# Schematic.net
KiCad netlist of a schematic drawn in Altium Designer
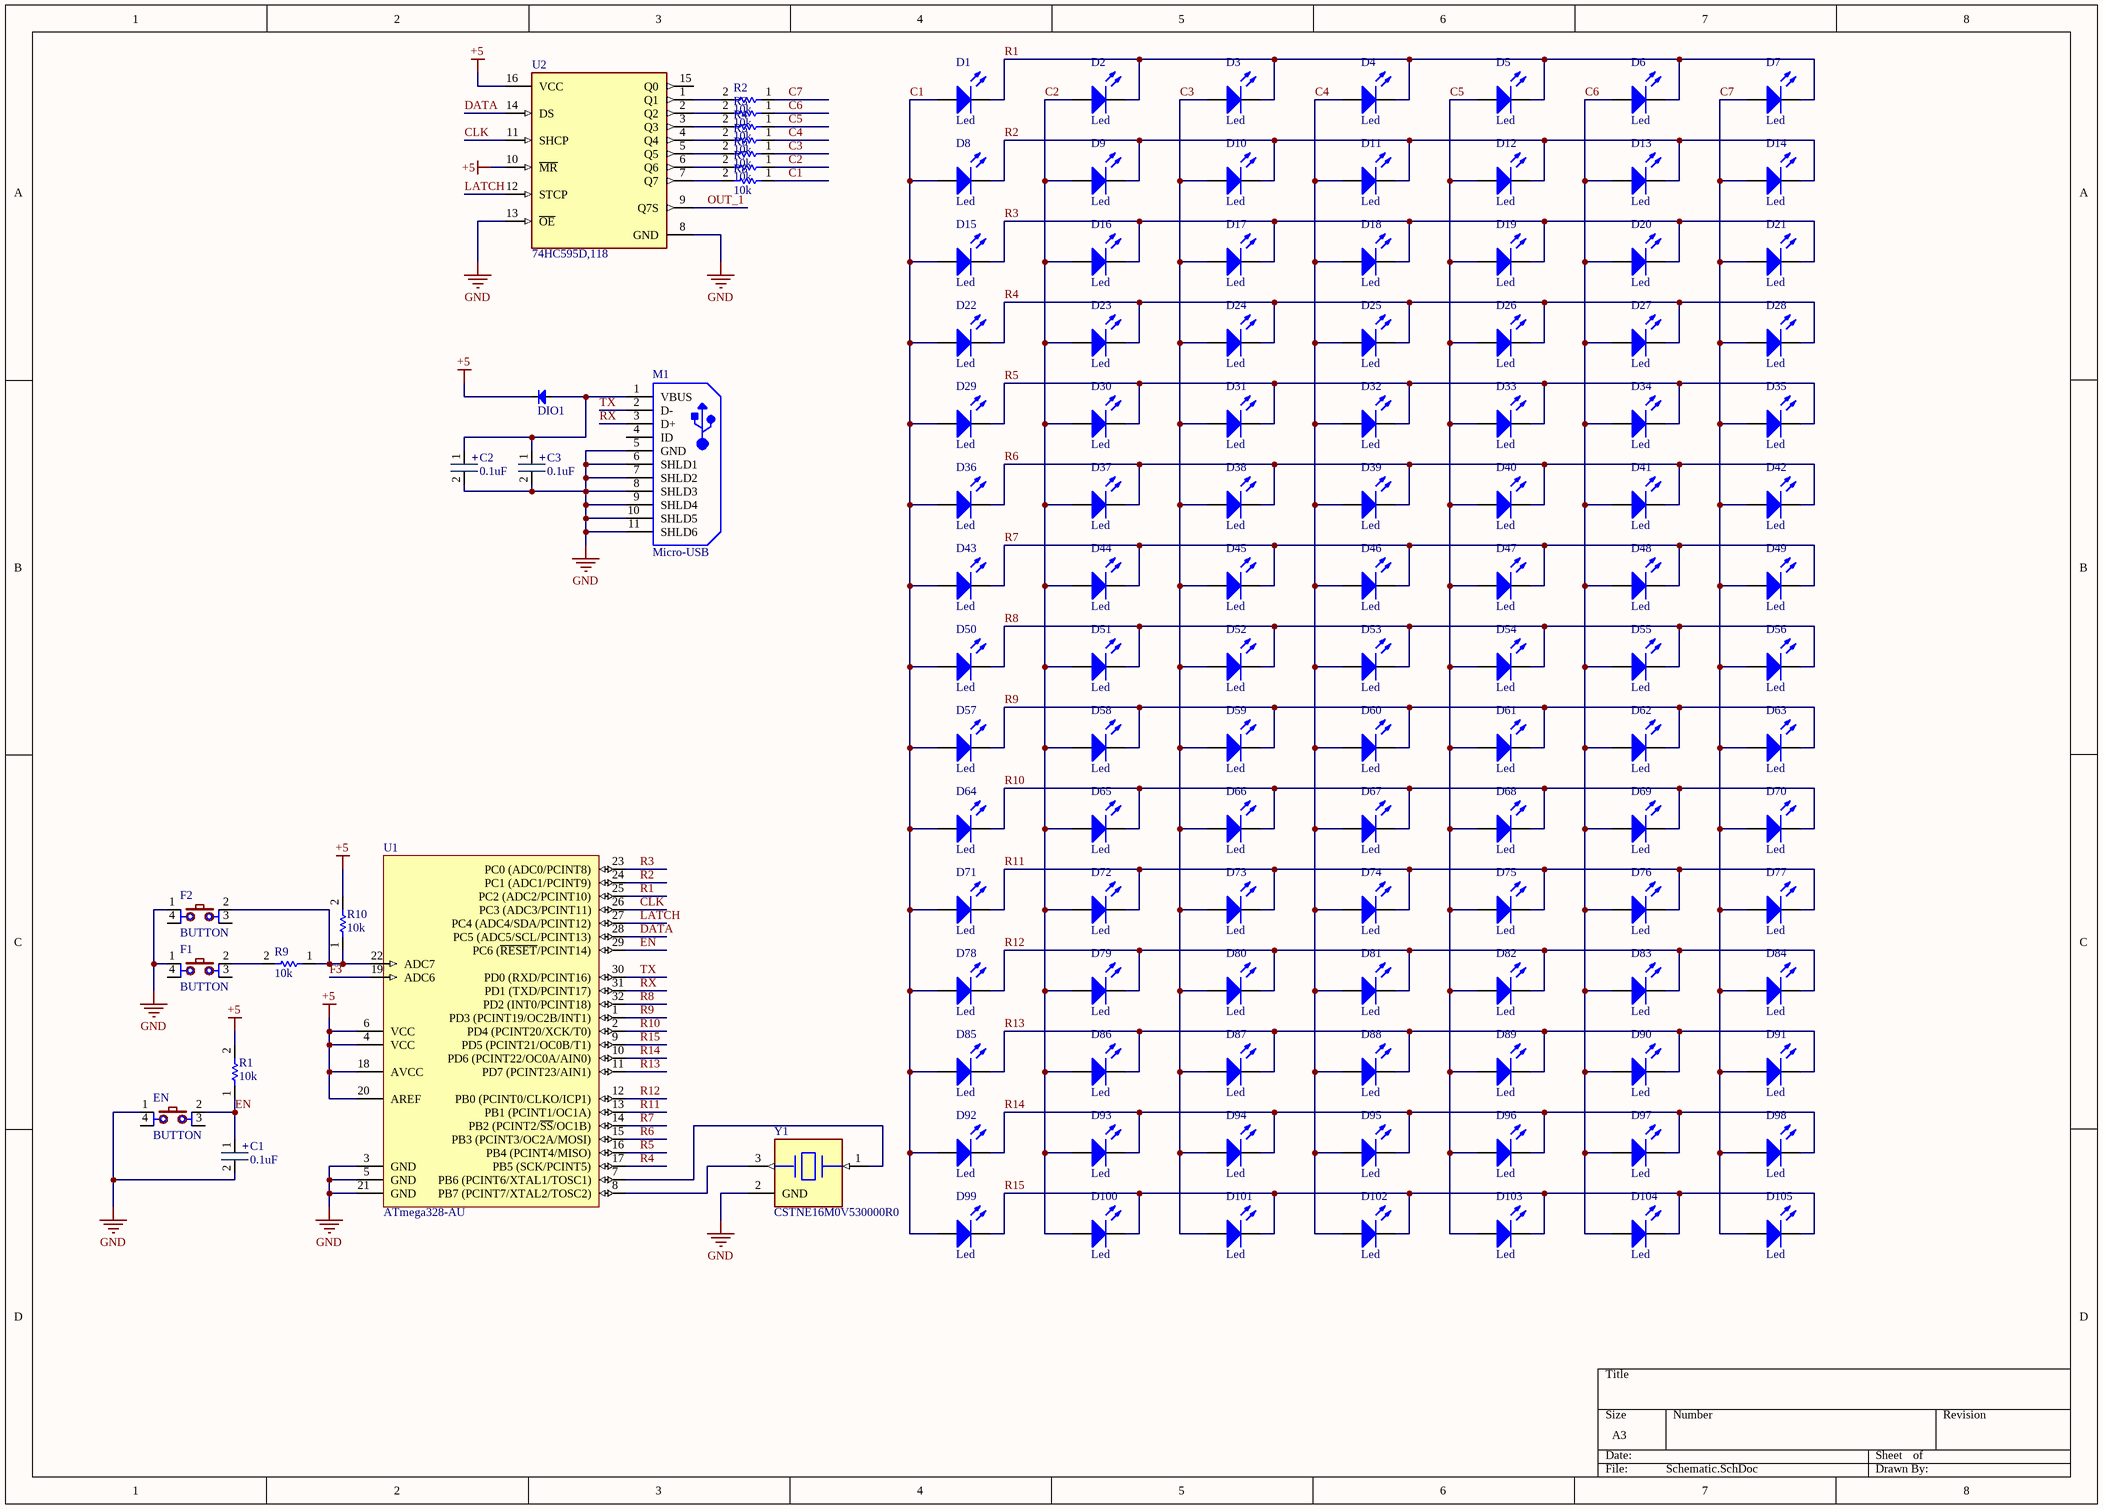
[diagram p0: Schematic.SchDoc]

(export (version "E")
  (design (tool "Eeschema 10.0.6"))
  (components
    (comp (ref "C1")
      (value "0.1uF")
      (footprint "Cap_0603_A")
      (description "General Purpose Ceramic Capacitor, 0603, 1nF, 10%, X7R, 15%, 50V")
      (fields (field (name "VOLTAGE") "50V") (field (name "TOLERANCE") "10%"))
      (libsource (lib "ResCapTransDio") (part "Capacitor"))
    )
    (comp (ref "C2")
      (value "0.1uF")
      (footprint "Cap_0603_A")
      (description "General Purpose Ceramic Capacitor, 0603, 1nF, 10%, X7R, 15%, 50V")
      (fields (field (name "VOLTAGE") "50V") (field (name "TOLERANCE") "10%"))
      (libsource (lib "ResCapTransDio") (part "Capacitor"))
    )
    (comp (ref "C3")
      (value "0.1uF")
      (footprint "Cap_0603_A")
      (description "General Purpose Ceramic Capacitor, 0603, 1nF, 10%, X7R, 15%, 50V")
      (fields (field (name "VOLTAGE") "50V") (field (name "TOLERANCE") "10%"))
      (libsource (lib "ResCapTransDio") (part "Capacitor"))
    )
    (comp (ref "D1") (value "Led") (footprint "LED 0603") (libsource (lib "ResCapTransDio") (part "Led")))
    (comp (ref "D2") (value "Led") (footprint "LED 0603") (libsource (lib "ResCapTransDio") (part "Led")))
    (comp (ref "D3") (value "Led") (footprint "LED 0603") (libsource (lib "ResCapTransDio") (part "Led")))
    (comp (ref "D4") (value "Led") (footprint "LED 0603") (libsource (lib "ResCapTransDio") (part "Led")))
    (comp (ref "D5") (value "Led") (footprint "LED 0603") (libsource (lib "ResCapTransDio") (part "Led")))
    (comp (ref "D6") (value "Led") (footprint "LED 0603") (libsource (lib "ResCapTransDio") (part "Led")))
    (comp (ref "D7") (value "Led") (footprint "LED 0603") (libsource (lib "ResCapTransDio") (part "Led")))
    (comp (ref "D8") (value "Led") (footprint "LED 0603") (libsource (lib "ResCapTransDio") (part "Led")))
    (comp (ref "D9") (value "Led") (footprint "LED 0603") (libsource (lib "ResCapTransDio") (part "Led")))
    (comp (ref "D10") (value "Led") (footprint "LED 0603") (libsource (lib "ResCapTransDio") (part "Led")))
    (comp (ref "D11") (value "Led") (footprint "LED 0603") (libsource (lib "ResCapTransDio") (part "Led")))
    (comp (ref "D12") (value "Led") (footprint "LED 0603") (libsource (lib "ResCapTransDio") (part "Led")))
    (comp (ref "D13") (value "Led") (footprint "LED 0603") (libsource (lib "ResCapTransDio") (part "Led")))
    (comp (ref "D14") (value "Led") (footprint "LED 0603") (libsource (lib "ResCapTransDio") (part "Led")))
    (comp (ref "D15") (value "Led") (footprint "LED 0603") (libsource (lib "ResCapTransDio") (part "Led")))
    (comp (ref "D16") (value "Led") (footprint "LED 0603") (libsource (lib "ResCapTransDio") (part "Led")))
    (comp (ref "D17") (value "Led") (footprint "LED 0603") (libsource (lib "ResCapTransDio") (part "Led")))
    (comp (ref "D18") (value "Led") (footprint "LED 0603") (libsource (lib "ResCapTransDio") (part "Led")))
    (comp (ref "D19") (value "Led") (footprint "LED 0603") (libsource (lib "ResCapTransDio") (part "Led")))
    (comp (ref "D20") (value "Led") (footprint "LED 0603") (libsource (lib "ResCapTransDio") (part "Led")))
    (comp (ref "D21") (value "Led") (footprint "LED 0603") (libsource (lib "ResCapTransDio") (part "Led")))
    (comp (ref "D22") (value "Led") (footprint "LED 0603") (libsource (lib "ResCapTransDio") (part "Led")))
    (comp (ref "D23") (value "Led") (footprint "LED 0603") (libsource (lib "ResCapTransDio") (part "Led")))
    (comp (ref "D24") (value "Led") (footprint "LED 0603") (libsource (lib "ResCapTransDio") (part "Led")))
    (comp (ref "D25") (value "Led") (footprint "LED 0603") (libsource (lib "ResCapTransDio") (part "Led")))
    (comp (ref "D26") (value "Led") (footprint "LED 0603") (libsource (lib "ResCapTransDio") (part "Led")))
    (comp (ref "D27") (value "Led") (footprint "LED 0603") (libsource (lib "ResCapTransDio") (part "Led")))
    (comp (ref "D28") (value "Led") (footprint "LED 0603") (libsource (lib "ResCapTransDio") (part "Led")))
    (comp (ref "D29") (value "Led") (footprint "LED 0603") (libsource (lib "ResCapTransDio") (part "Led")))
    (comp (ref "D30") (value "Led") (footprint "LED 0603") (libsource (lib "ResCapTransDio") (part "Led")))
    (comp (ref "D31") (value "Led") (footprint "LED 0603") (libsource (lib "ResCapTransDio") (part "Led")))
    (comp (ref "D32") (value "Led") (footprint "LED 0603") (libsource (lib "ResCapTransDio") (part "Led")))
    (comp (ref "D33") (value "Led") (footprint "LED 0603") (libsource (lib "ResCapTransDio") (part "Led")))
    (comp (ref "D34") (value "Led") (footprint "LED 0603") (libsource (lib "ResCapTransDio") (part "Led")))
    (comp (ref "D35") (value "Led") (footprint "LED 0603") (libsource (lib "ResCapTransDio") (part "Led")))
    (comp (ref "D36") (value "Led") (footprint "LED 0603") (libsource (lib "ResCapTransDio") (part "Led")))
    (comp (ref "D37") (value "Led") (footprint "LED 0603") (libsource (lib "ResCapTransDio") (part "Led")))
    (comp (ref "D38") (value "Led") (footprint "LED 0603") (libsource (lib "ResCapTransDio") (part "Led")))
    (comp (ref "D39") (value "Led") (footprint "LED 0603") (libsource (lib "ResCapTransDio") (part "Led")))
    (comp (ref "D40") (value "Led") (footprint "LED 0603") (libsource (lib "ResCapTransDio") (part "Led")))
    (comp (ref "D41") (value "Led") (footprint "LED 0603") (libsource (lib "ResCapTransDio") (part "Led")))
    (comp (ref "D42") (value "Led") (footprint "LED 0603") (libsource (lib "ResCapTransDio") (part "Led")))
    (comp (ref "D43") (value "Led") (footprint "LED 0603") (libsource (lib "ResCapTransDio") (part "Led")))
    (comp (ref "D44") (value "Led") (footprint "LED 0603") (libsource (lib "ResCapTransDio") (part "Led")))
    (comp (ref "D45") (value "Led") (footprint "LED 0603") (libsource (lib "ResCapTransDio") (part "Led")))
    (comp (ref "D46") (value "Led") (footprint "LED 0603") (libsource (lib "ResCapTransDio") (part "Led")))
    (comp (ref "D47") (value "Led") (footprint "LED 0603") (libsource (lib "ResCapTransDio") (part "Led")))
    (comp (ref "D48") (value "Led") (footprint "LED 0603") (libsource (lib "ResCapTransDio") (part "Led")))
    (comp (ref "D49") (value "Led") (footprint "LED 0603") (libsource (lib "ResCapTransDio") (part "Led")))
    (comp (ref "D50") (value "Led") (footprint "LED 0603") (libsource (lib "ResCapTransDio") (part "Led")))
    (comp (ref "D51") (value "Led") (footprint "LED 0603") (libsource (lib "ResCapTransDio") (part "Led")))
    (comp (ref "D52") (value "Led") (footprint "LED 0603") (libsource (lib "ResCapTransDio") (part "Led")))
    (comp (ref "D53") (value "Led") (footprint "LED 0603") (libsource (lib "ResCapTransDio") (part "Led")))
    (comp (ref "D54") (value "Led") (footprint "LED 0603") (libsource (lib "ResCapTransDio") (part "Led")))
    (comp (ref "D55") (value "Led") (footprint "LED 0603") (libsource (lib "ResCapTransDio") (part "Led")))
    (comp (ref "D56") (value "Led") (footprint "LED 0603") (libsource (lib "ResCapTransDio") (part "Led")))
    (comp (ref "D57") (value "Led") (footprint "LED 0603") (libsource (lib "ResCapTransDio") (part "Led")))
    (comp (ref "D58") (value "Led") (footprint "LED 0603") (libsource (lib "ResCapTransDio") (part "Led")))
    (comp (ref "D59") (value "Led") (footprint "LED 0603") (libsource (lib "ResCapTransDio") (part "Led")))
    (comp (ref "D60") (value "Led") (footprint "LED 0603") (libsource (lib "ResCapTransDio") (part "Led")))
    (comp (ref "D61") (value "Led") (footprint "LED 0603") (libsource (lib "ResCapTransDio") (part "Led")))
    (comp (ref "D62") (value "Led") (footprint "LED 0603") (libsource (lib "ResCapTransDio") (part "Led")))
    (comp (ref "D63") (value "Led") (footprint "LED 0603") (libsource (lib "ResCapTransDio") (part "Led")))
    (comp (ref "D64") (value "Led") (footprint "LED 0603") (libsource (lib "ResCapTransDio") (part "Led")))
    (comp (ref "D65") (value "Led") (footprint "LED 0603") (libsource (lib "ResCapTransDio") (part "Led")))
    (comp (ref "D66") (value "Led") (footprint "LED 0603") (libsource (lib "ResCapTransDio") (part "Led")))
    (comp (ref "D67") (value "Led") (footprint "LED 0603") (libsource (lib "ResCapTransDio") (part "Led")))
    (comp (ref "D68") (value "Led") (footprint "LED 0603") (libsource (lib "ResCapTransDio") (part "Led")))
    (comp (ref "D69") (value "Led") (footprint "LED 0603") (libsource (lib "ResCapTransDio") (part "Led")))
    (comp (ref "D70") (value "Led") (footprint "LED 0603") (libsource (lib "ResCapTransDio") (part "Led")))
    (comp (ref "D71") (value "Led") (footprint "LED 0603") (libsource (lib "ResCapTransDio") (part "Led")))
    (comp (ref "D72") (value "Led") (footprint "LED 0603") (libsource (lib "ResCapTransDio") (part "Led")))
    (comp (ref "D73") (value "Led") (footprint "LED 0603") (libsource (lib "ResCapTransDio") (part "Led")))
    (comp (ref "D74") (value "Led") (footprint "LED 0603") (libsource (lib "ResCapTransDio") (part "Led")))
    (comp (ref "D75") (value "Led") (footprint "LED 0603") (libsource (lib "ResCapTransDio") (part "Led")))
    (comp (ref "D76") (value "Led") (footprint "LED 0603") (libsource (lib "ResCapTransDio") (part "Led")))
    (comp (ref "D77") (value "Led") (footprint "LED 0603") (libsource (lib "ResCapTransDio") (part "Led")))
    (comp (ref "D78") (value "Led") (footprint "LED 0603") (libsource (lib "ResCapTransDio") (part "Led")))
    (comp (ref "D79") (value "Led") (footprint "LED 0603") (libsource (lib "ResCapTransDio") (part "Led")))
    (comp (ref "D80") (value "Led") (footprint "LED 0603") (libsource (lib "ResCapTransDio") (part "Led")))
    (comp (ref "D81") (value "Led") (footprint "LED 0603") (libsource (lib "ResCapTransDio") (part "Led")))
    (comp (ref "D82") (value "Led") (footprint "LED 0603") (libsource (lib "ResCapTransDio") (part "Led")))
    (comp (ref "D83") (value "Led") (footprint "LED 0603") (libsource (lib "ResCapTransDio") (part "Led")))
    (comp (ref "D84") (value "Led") (footprint "LED 0603") (libsource (lib "ResCapTransDio") (part "Led")))
    (comp (ref "D85") (value "Led") (footprint "LED 0603") (libsource (lib "ResCapTransDio") (part "Led")))
    (comp (ref "D86") (value "Led") (footprint "LED 0603") (libsource (lib "ResCapTransDio") (part "Led")))
    (comp (ref "D87") (value "Led") (footprint "LED 0603") (libsource (lib "ResCapTransDio") (part "Led")))
    (comp (ref "D88") (value "Led") (footprint "LED 0603") (libsource (lib "ResCapTransDio") (part "Led")))
    (comp (ref "D89") (value "Led") (footprint "LED 0603") (libsource (lib "ResCapTransDio") (part "Led")))
    (comp (ref "D90") (value "Led") (footprint "LED 0603") (libsource (lib "ResCapTransDio") (part "Led")))
    (comp (ref "D91") (value "Led") (footprint "LED 0603") (libsource (lib "ResCapTransDio") (part "Led")))
    (comp (ref "D92") (value "Led") (footprint "LED 0603") (libsource (lib "ResCapTransDio") (part "Led")))
    (comp (ref "D93") (value "Led") (footprint "LED 0603") (libsource (lib "ResCapTransDio") (part "Led")))
    (comp (ref "D94") (value "Led") (footprint "LED 0603") (libsource (lib "ResCapTransDio") (part "Led")))
    (comp (ref "D95") (value "Led") (footprint "LED 0603") (libsource (lib "ResCapTransDio") (part "Led")))
    (comp (ref "D96") (value "Led") (footprint "LED 0603") (libsource (lib "ResCapTransDio") (part "Led")))
    (comp (ref "D97") (value "Led") (footprint "LED 0603") (libsource (lib "ResCapTransDio") (part "Led")))
    (comp (ref "D98") (value "Led") (footprint "LED 0603") (libsource (lib "ResCapTransDio") (part "Led")))
    (comp (ref "D99") (value "Led") (footprint "LED 0603") (libsource (lib "ResCapTransDio") (part "Led")))
    (comp (ref "D100") (value "Led") (footprint "LED 0603") (libsource (lib "ResCapTransDio") (part "Led")))
    (comp (ref "D101") (value "Led") (footprint "LED 0603") (libsource (lib "ResCapTransDio") (part "Led")))
    (comp (ref "D102") (value "Led") (footprint "LED 0603") (libsource (lib "ResCapTransDio") (part "Led")))
    (comp (ref "D103") (value "Led") (footprint "LED 0603") (libsource (lib "ResCapTransDio") (part "Led")))
    (comp (ref "D104") (value "Led") (footprint "LED 0603") (libsource (lib "ResCapTransDio") (part "Led")))
    (comp (ref "D105") (value "Led") (footprint "LED 0603") (libsource (lib "ResCapTransDio") (part "Led")))
    (comp (ref "DIO1")
      (value "Diode SMD")
      (footprint "DIO-SMD-106")
      (description "Default Diode")
      (fields (field (name "PUBLISHER") "Altium Limited"))
      (libsource (lib "TechMT.VN_Lib_Project v2") (part "Diode SMD"))
    )
    (comp (ref "EN")
      (value "BUTTON")
      (footprint "BUTTON 3x4mm 2 Pin")
      (libsource (lib "Librarys") (part "BUTTON 4 PIN"))
    )
    (comp (ref "F1")
      (value "BUTTON")
      (footprint "BUTTON 3x4mm 2 Pin")
      (libsource (lib "Librarys") (part "BUTTON 4 PIN"))
    )
    (comp (ref "F2")
      (value "BUTTON")
      (footprint "BUTTON 3x4mm 2 Pin")
      (libsource (lib "Librarys") (part "BUTTON 4 PIN"))
    )
    (comp (ref "M1")
      (value "Micro-USB")
      (footprint "2.0 5 PIN SMD")
      (libsource (lib "Librarys") (part "Micro-USB"))
    )
    (comp (ref "R1")
      (value "10k")
      (footprint "Res_0603")
      (libsource (lib "ResCapTransDio") (part "Resistor"))
    )
    (comp (ref "R2")
      (value "10k")
      (footprint "Res_0603")
      (libsource (lib "ResCapTransDio") (part "Resistor"))
    )
    (comp (ref "R3")
      (value "10k")
      (footprint "Res_0603")
      (libsource (lib "ResCapTransDio") (part "Resistor"))
    )
    (comp (ref "R4")
      (value "10k")
      (footprint "Res_0603")
      (libsource (lib "ResCapTransDio") (part "Resistor"))
    )
    (comp (ref "R5")
      (value "10k")
      (footprint "Res_0603")
      (libsource (lib "ResCapTransDio") (part "Resistor"))
    )
    (comp (ref "R6")
      (value "10k")
      (footprint "Res_0603")
      (libsource (lib "ResCapTransDio") (part "Resistor"))
    )
    (comp (ref "R7")
      (value "10k")
      (footprint "Res_0603")
      (libsource (lib "ResCapTransDio") (part "Resistor"))
    )
    (comp (ref "R8")
      (value "10k")
      (footprint "Res_0603")
      (libsource (lib "ResCapTransDio") (part "Resistor"))
    )
    (comp (ref "R9")
      (value "10k")
      (footprint "Res_0603")
      (libsource (lib "ResCapTransDio") (part "Resistor"))
    )
    (comp (ref "R10")
      (value "10k")
      (footprint "Res_0603")
      (libsource (lib "ResCapTransDio") (part "Resistor"))
    )
    (comp (ref "U1")
      (value "ATmega328-AU")
      (footprint "TQFP32")
      (fields (field (name "PUBLISHER") "Altium Limited"))
      (libsource (lib "TechMT.VN_Lib_Project v2") (part "ATmega328-AU"))
    )
    (comp (ref "U2")
      (value "74HC595D,118")
      (footprint "FP-SOT109-1-IPC_C")
      (description "IC SHIFT REGISTER 8BIT 16SOIC")
      (libsource (lib "Altium Content Vault") (part "7b153f231cfcc3ac06dee253bd56617"))
    )
    (comp (ref "Y1")
      (value "CSTNE16M0V530000R0")
      (footprint "FP-CSTNE16M0V530000R0-MFG")
      (description "CERAMIC RES 16.0000MHZ 15PF SMD")
      (fields (field (name "TOLERANCE") "0.5%") (field (name "MANUFACTURER") "Murata"))
      (libsource (lib "Altium Content Vault") (part "f88508b02107a2c8e6f46217c19d2b8"))
    )
  )
  (nets
    (net (code "1") (name "+5") (class "Default")
      (node (ref "DIO1") (pin "2") (pinfunction "K_2") (pintype "passive"))
      (node (ref "R1") (pin "2") (pinfunction "2_2") (pintype "passive"))
      (node (ref "R10") (pin "2") (pinfunction "2_2") (pintype "passive"))
      (node (ref "U1") (pin "18") (pinfunction "AVCC_18") (pintype "power_in"))
      (node (ref "U1") (pin "20") (pinfunction "AREF_20") (pintype "passive"))
      (node (ref "U1") (pin "4") (pinfunction "VCC_4") (pintype "power_in"))
      (node (ref "U1") (pin "6") (pinfunction "VCC_6") (pintype "power_in"))
      (node (ref "U2") (pin "10") (pinfunction "~{MR}_10") (pintype "input"))
      (node (ref "U2") (pin "16") (pinfunction "VCC_16") (pintype "power_in"))
    )
    (net (code "2") (name "/C1") (class "Default")
      (node (ref "D1") (pin "1") (pinfunction "A_1") (pintype "passive"))
      (node (ref "D15") (pin "1") (pinfunction "A_1") (pintype "passive"))
      (node (ref "D22") (pin "1") (pinfunction "A_1") (pintype "passive"))
      (node (ref "D29") (pin "1") (pinfunction "A_1") (pintype "passive"))
      (node (ref "D36") (pin "1") (pinfunction "A_1") (pintype "passive"))
      (node (ref "D43") (pin "1") (pinfunction "A_1") (pintype "passive"))
      (node (ref "D50") (pin "1") (pinfunction "A_1") (pintype "passive"))
      (node (ref "D57") (pin "1") (pinfunction "A_1") (pintype "passive"))
      (node (ref "D64") (pin "1") (pinfunction "A_1") (pintype "passive"))
      (node (ref "D71") (pin "1") (pinfunction "A_1") (pintype "passive"))
      (node (ref "D78") (pin "1") (pinfunction "A_1") (pintype "passive"))
      (node (ref "D8") (pin "1") (pinfunction "A_1") (pintype "passive"))
      (node (ref "D85") (pin "1") (pinfunction "A_1") (pintype "passive"))
      (node (ref "D92") (pin "1") (pinfunction "A_1") (pintype "passive"))
      (node (ref "D99") (pin "1") (pinfunction "A_1") (pintype "passive"))
      (node (ref "R8") (pin "1") (pinfunction "1_1") (pintype "passive"))
    )
    (net (code "3") (name "/C2") (class "Default")
      (node (ref "D100") (pin "1") (pinfunction "A_1") (pintype "passive"))
      (node (ref "D16") (pin "1") (pinfunction "A_1") (pintype "passive"))
      (node (ref "D2") (pin "1") (pinfunction "A_1") (pintype "passive"))
      (node (ref "D23") (pin "1") (pinfunction "A_1") (pintype "passive"))
      (node (ref "D30") (pin "1") (pinfunction "A_1") (pintype "passive"))
      (node (ref "D37") (pin "1") (pinfunction "A_1") (pintype "passive"))
      (node (ref "D44") (pin "1") (pinfunction "A_1") (pintype "passive"))
      (node (ref "D51") (pin "1") (pinfunction "A_1") (pintype "passive"))
      (node (ref "D58") (pin "1") (pinfunction "A_1") (pintype "passive"))
      (node (ref "D65") (pin "1") (pinfunction "A_1") (pintype "passive"))
      (node (ref "D72") (pin "1") (pinfunction "A_1") (pintype "passive"))
      (node (ref "D79") (pin "1") (pinfunction "A_1") (pintype "passive"))
      (node (ref "D86") (pin "1") (pinfunction "A_1") (pintype "passive"))
      (node (ref "D9") (pin "1") (pinfunction "A_1") (pintype "passive"))
      (node (ref "D93") (pin "1") (pinfunction "A_1") (pintype "passive"))
      (node (ref "R7") (pin "1") (pinfunction "1_1") (pintype "passive"))
    )
    (net (code "4") (name "/C3") (class "Default")
      (node (ref "D10") (pin "1") (pinfunction "A_1") (pintype "passive"))
      (node (ref "D101") (pin "1") (pinfunction "A_1") (pintype "passive"))
      (node (ref "D17") (pin "1") (pinfunction "A_1") (pintype "passive"))
      (node (ref "D24") (pin "1") (pinfunction "A_1") (pintype "passive"))
      (node (ref "D3") (pin "1") (pinfunction "A_1") (pintype "passive"))
      (node (ref "D31") (pin "1") (pinfunction "A_1") (pintype "passive"))
      (node (ref "D38") (pin "1") (pinfunction "A_1") (pintype "passive"))
      (node (ref "D45") (pin "1") (pinfunction "A_1") (pintype "passive"))
      (node (ref "D52") (pin "1") (pinfunction "A_1") (pintype "passive"))
      (node (ref "D59") (pin "1") (pinfunction "A_1") (pintype "passive"))
      (node (ref "D66") (pin "1") (pinfunction "A_1") (pintype "passive"))
      (node (ref "D73") (pin "1") (pinfunction "A_1") (pintype "passive"))
      (node (ref "D80") (pin "1") (pinfunction "A_1") (pintype "passive"))
      (node (ref "D87") (pin "1") (pinfunction "A_1") (pintype "passive"))
      (node (ref "D94") (pin "1") (pinfunction "A_1") (pintype "passive"))
      (node (ref "R6") (pin "1") (pinfunction "1_1") (pintype "passive"))
    )
    (net (code "5") (name "/C4") (class "Default")
      (node (ref "D102") (pin "1") (pinfunction "A_1") (pintype "passive"))
      (node (ref "D11") (pin "1") (pinfunction "A_1") (pintype "passive"))
      (node (ref "D18") (pin "1") (pinfunction "A_1") (pintype "passive"))
      (node (ref "D25") (pin "1") (pinfunction "A_1") (pintype "passive"))
      (node (ref "D32") (pin "1") (pinfunction "A_1") (pintype "passive"))
      (node (ref "D39") (pin "1") (pinfunction "A_1") (pintype "passive"))
      (node (ref "D4") (pin "1") (pinfunction "A_1") (pintype "passive"))
      (node (ref "D46") (pin "1") (pinfunction "A_1") (pintype "passive"))
      (node (ref "D53") (pin "1") (pinfunction "A_1") (pintype "passive"))
      (node (ref "D60") (pin "1") (pinfunction "A_1") (pintype "passive"))
      (node (ref "D67") (pin "1") (pinfunction "A_1") (pintype "passive"))
      (node (ref "D74") (pin "1") (pinfunction "A_1") (pintype "passive"))
      (node (ref "D81") (pin "1") (pinfunction "A_1") (pintype "passive"))
      (node (ref "D88") (pin "1") (pinfunction "A_1") (pintype "passive"))
      (node (ref "D95") (pin "1") (pinfunction "A_1") (pintype "passive"))
      (node (ref "R5") (pin "1") (pinfunction "1_1") (pintype "passive"))
    )
    (net (code "6") (name "/C5") (class "Default")
      (node (ref "D103") (pin "1") (pinfunction "A_1") (pintype "passive"))
      (node (ref "D12") (pin "1") (pinfunction "A_1") (pintype "passive"))
      (node (ref "D19") (pin "1") (pinfunction "A_1") (pintype "passive"))
      (node (ref "D26") (pin "1") (pinfunction "A_1") (pintype "passive"))
      (node (ref "D33") (pin "1") (pinfunction "A_1") (pintype "passive"))
      (node (ref "D40") (pin "1") (pinfunction "A_1") (pintype "passive"))
      (node (ref "D47") (pin "1") (pinfunction "A_1") (pintype "passive"))
      (node (ref "D5") (pin "1") (pinfunction "A_1") (pintype "passive"))
      (node (ref "D54") (pin "1") (pinfunction "A_1") (pintype "passive"))
      (node (ref "D61") (pin "1") (pinfunction "A_1") (pintype "passive"))
      (node (ref "D68") (pin "1") (pinfunction "A_1") (pintype "passive"))
      (node (ref "D75") (pin "1") (pinfunction "A_1") (pintype "passive"))
      (node (ref "D82") (pin "1") (pinfunction "A_1") (pintype "passive"))
      (node (ref "D89") (pin "1") (pinfunction "A_1") (pintype "passive"))
      (node (ref "D96") (pin "1") (pinfunction "A_1") (pintype "passive"))
      (node (ref "R4") (pin "1") (pinfunction "1_1") (pintype "passive"))
    )
    (net (code "7") (name "/C6") (class "Default")
      (node (ref "D104") (pin "1") (pinfunction "A_1") (pintype "passive"))
      (node (ref "D13") (pin "1") (pinfunction "A_1") (pintype "passive"))
      (node (ref "D20") (pin "1") (pinfunction "A_1") (pintype "passive"))
      (node (ref "D27") (pin "1") (pinfunction "A_1") (pintype "passive"))
      (node (ref "D34") (pin "1") (pinfunction "A_1") (pintype "passive"))
      (node (ref "D41") (pin "1") (pinfunction "A_1") (pintype "passive"))
      (node (ref "D48") (pin "1") (pinfunction "A_1") (pintype "passive"))
      (node (ref "D55") (pin "1") (pinfunction "A_1") (pintype "passive"))
      (node (ref "D6") (pin "1") (pinfunction "A_1") (pintype "passive"))
      (node (ref "D62") (pin "1") (pinfunction "A_1") (pintype "passive"))
      (node (ref "D69") (pin "1") (pinfunction "A_1") (pintype "passive"))
      (node (ref "D76") (pin "1") (pinfunction "A_1") (pintype "passive"))
      (node (ref "D83") (pin "1") (pinfunction "A_1") (pintype "passive"))
      (node (ref "D90") (pin "1") (pinfunction "A_1") (pintype "passive"))
      (node (ref "D97") (pin "1") (pinfunction "A_1") (pintype "passive"))
      (node (ref "R3") (pin "1") (pinfunction "1_1") (pintype "passive"))
    )
    (net (code "8") (name "/C7") (class "Default")
      (node (ref "D105") (pin "1") (pinfunction "A_1") (pintype "passive"))
      (node (ref "D14") (pin "1") (pinfunction "A_1") (pintype "passive"))
      (node (ref "D21") (pin "1") (pinfunction "A_1") (pintype "passive"))
      (node (ref "D28") (pin "1") (pinfunction "A_1") (pintype "passive"))
      (node (ref "D35") (pin "1") (pinfunction "A_1") (pintype "passive"))
      (node (ref "D42") (pin "1") (pinfunction "A_1") (pintype "passive"))
      (node (ref "D49") (pin "1") (pinfunction "A_1") (pintype "passive"))
      (node (ref "D56") (pin "1") (pinfunction "A_1") (pintype "passive"))
      (node (ref "D63") (pin "1") (pinfunction "A_1") (pintype "passive"))
      (node (ref "D7") (pin "1") (pinfunction "A_1") (pintype "passive"))
      (node (ref "D70") (pin "1") (pinfunction "A_1") (pintype "passive"))
      (node (ref "D77") (pin "1") (pinfunction "A_1") (pintype "passive"))
      (node (ref "D84") (pin "1") (pinfunction "A_1") (pintype "passive"))
      (node (ref "D91") (pin "1") (pinfunction "A_1") (pintype "passive"))
      (node (ref "D98") (pin "1") (pinfunction "A_1") (pintype "passive"))
      (node (ref "R2") (pin "1") (pinfunction "1_1") (pintype "passive"))
    )
    (net (code "9") (name "/CLK") (class "Default")
      (node (ref "U1") (pin "26") (pinfunction "PC3_(ADC3/PCINT11)_26") (pintype "bidirectional"))
      (node (ref "U2") (pin "11") (pinfunction "SHCP_11") (pintype "input"))
    )
    (net (code "10") (name "/DATA") (class "Default")
      (node (ref "U1") (pin "28") (pinfunction "PC5_(ADC5/SCL/PCINT13)_28") (pintype "bidirectional"))
      (node (ref "U2") (pin "14") (pinfunction "DS_14") (pintype "input"))
    )
    (net (code "11") (name "/EN") (class "Default")
      (node (ref "C1") (pin "1") (pinfunction "1_1") (pintype "passive"))
      (node (ref "EN") (pin "2") (pinfunction "2_2") (pintype "passive"))
      (node (ref "R1") (pin "1") (pinfunction "1_1") (pintype "passive"))
      (node (ref "U1") (pin "29") (pinfunction "PC6_(~{RESET}/PCINT14)_29") (pintype "bidirectional"))
    )
    (net (code "12") (name "/F3") (class "Default")
      (node (ref "U1") (pin "19") (pinfunction "ADC6_19") (pintype "input"))
    )
    (net (code "13") (name "/LATCH") (class "Default")
      (node (ref "U1") (pin "27") (pinfunction "PC4_(ADC4/SDA/PCINT12)_27") (pintype "bidirectional"))
      (node (ref "U2") (pin "12") (pinfunction "STCP_12") (pintype "input"))
    )
    (net (code "14") (name "/OUT_1") (class "Default")
      (node (ref "U2") (pin "9") (pinfunction "Q7S_9") (pintype "output"))
    )
    (net (code "15") (name "/R1") (class "Default")
      (node (ref "D1") (pin "2") (pinfunction "K_2") (pintype "passive"))
      (node (ref "D2") (pin "2") (pinfunction "K_2") (pintype "passive"))
      (node (ref "D3") (pin "2") (pinfunction "K_2") (pintype "passive"))
      (node (ref "D4") (pin "2") (pinfunction "K_2") (pintype "passive"))
      (node (ref "D5") (pin "2") (pinfunction "K_2") (pintype "passive"))
      (node (ref "D6") (pin "2") (pinfunction "K_2") (pintype "passive"))
      (node (ref "D7") (pin "2") (pinfunction "K_2") (pintype "passive"))
      (node (ref "U1") (pin "25") (pinfunction "PC2_(ADC2/PCINT10)_25") (pintype "bidirectional"))
    )
    (net (code "16") (name "/R2") (class "Default")
      (node (ref "D10") (pin "2") (pinfunction "K_2") (pintype "passive"))
      (node (ref "D11") (pin "2") (pinfunction "K_2") (pintype "passive"))
      (node (ref "D12") (pin "2") (pinfunction "K_2") (pintype "passive"))
      (node (ref "D13") (pin "2") (pinfunction "K_2") (pintype "passive"))
      (node (ref "D14") (pin "2") (pinfunction "K_2") (pintype "passive"))
      (node (ref "D8") (pin "2") (pinfunction "K_2") (pintype "passive"))
      (node (ref "D9") (pin "2") (pinfunction "K_2") (pintype "passive"))
      (node (ref "U1") (pin "24") (pinfunction "PC1_(ADC1/PCINT9)_24") (pintype "bidirectional"))
    )
    (net (code "17") (name "/R3") (class "Default")
      (node (ref "D15") (pin "2") (pinfunction "K_2") (pintype "passive"))
      (node (ref "D16") (pin "2") (pinfunction "K_2") (pintype "passive"))
      (node (ref "D17") (pin "2") (pinfunction "K_2") (pintype "passive"))
      (node (ref "D18") (pin "2") (pinfunction "K_2") (pintype "passive"))
      (node (ref "D19") (pin "2") (pinfunction "K_2") (pintype "passive"))
      (node (ref "D20") (pin "2") (pinfunction "K_2") (pintype "passive"))
      (node (ref "D21") (pin "2") (pinfunction "K_2") (pintype "passive"))
      (node (ref "U1") (pin "23") (pinfunction "PC0_(ADC0/PCINT8)_23") (pintype "bidirectional"))
    )
    (net (code "18") (name "/R4") (class "Default")
      (node (ref "D22") (pin "2") (pinfunction "K_2") (pintype "passive"))
      (node (ref "D23") (pin "2") (pinfunction "K_2") (pintype "passive"))
      (node (ref "D24") (pin "2") (pinfunction "K_2") (pintype "passive"))
      (node (ref "D25") (pin "2") (pinfunction "K_2") (pintype "passive"))
      (node (ref "D26") (pin "2") (pinfunction "K_2") (pintype "passive"))
      (node (ref "D27") (pin "2") (pinfunction "K_2") (pintype "passive"))
      (node (ref "D28") (pin "2") (pinfunction "K_2") (pintype "passive"))
      (node (ref "U1") (pin "17") (pinfunction "PB5_(SCK/PCINT5)_17") (pintype "bidirectional"))
    )
    (net (code "19") (name "/R5") (class "Default")
      (node (ref "D29") (pin "2") (pinfunction "K_2") (pintype "passive"))
      (node (ref "D30") (pin "2") (pinfunction "K_2") (pintype "passive"))
      (node (ref "D31") (pin "2") (pinfunction "K_2") (pintype "passive"))
      (node (ref "D32") (pin "2") (pinfunction "K_2") (pintype "passive"))
      (node (ref "D33") (pin "2") (pinfunction "K_2") (pintype "passive"))
      (node (ref "D34") (pin "2") (pinfunction "K_2") (pintype "passive"))
      (node (ref "D35") (pin "2") (pinfunction "K_2") (pintype "passive"))
      (node (ref "U1") (pin "16") (pinfunction "PB4_(PCINT4/MISO)_16") (pintype "bidirectional"))
    )
    (net (code "20") (name "/R6") (class "Default")
      (node (ref "D36") (pin "2") (pinfunction "K_2") (pintype "passive"))
      (node (ref "D37") (pin "2") (pinfunction "K_2") (pintype "passive"))
      (node (ref "D38") (pin "2") (pinfunction "K_2") (pintype "passive"))
      (node (ref "D39") (pin "2") (pinfunction "K_2") (pintype "passive"))
      (node (ref "D40") (pin "2") (pinfunction "K_2") (pintype "passive"))
      (node (ref "D41") (pin "2") (pinfunction "K_2") (pintype "passive"))
      (node (ref "D42") (pin "2") (pinfunction "K_2") (pintype "passive"))
      (node (ref "U1") (pin "15") (pinfunction "PB3_(PCINT3/OC2A/MOSI)_15") (pintype "bidirectional"))
    )
    (net (code "21") (name "/R7") (class "Default")
      (node (ref "D43") (pin "2") (pinfunction "K_2") (pintype "passive"))
      (node (ref "D44") (pin "2") (pinfunction "K_2") (pintype "passive"))
      (node (ref "D45") (pin "2") (pinfunction "K_2") (pintype "passive"))
      (node (ref "D46") (pin "2") (pinfunction "K_2") (pintype "passive"))
      (node (ref "D47") (pin "2") (pinfunction "K_2") (pintype "passive"))
      (node (ref "D48") (pin "2") (pinfunction "K_2") (pintype "passive"))
      (node (ref "D49") (pin "2") (pinfunction "K_2") (pintype "passive"))
      (node (ref "U1") (pin "14") (pinfunction "PB2_(PCINT2/~{SS}/OC1B)_14") (pintype "bidirectional"))
    )
    (net (code "22") (name "/R8") (class "Default")
      (node (ref "D50") (pin "2") (pinfunction "K_2") (pintype "passive"))
      (node (ref "D51") (pin "2") (pinfunction "K_2") (pintype "passive"))
      (node (ref "D52") (pin "2") (pinfunction "K_2") (pintype "passive"))
      (node (ref "D53") (pin "2") (pinfunction "K_2") (pintype "passive"))
      (node (ref "D54") (pin "2") (pinfunction "K_2") (pintype "passive"))
      (node (ref "D55") (pin "2") (pinfunction "K_2") (pintype "passive"))
      (node (ref "D56") (pin "2") (pinfunction "K_2") (pintype "passive"))
      (node (ref "U1") (pin "32") (pinfunction "PD2_(INT0/PCINT18)_32") (pintype "bidirectional"))
    )
    (net (code "23") (name "/R9") (class "Default")
      (node (ref "D57") (pin "2") (pinfunction "K_2") (pintype "passive"))
      (node (ref "D58") (pin "2") (pinfunction "K_2") (pintype "passive"))
      (node (ref "D59") (pin "2") (pinfunction "K_2") (pintype "passive"))
      (node (ref "D60") (pin "2") (pinfunction "K_2") (pintype "passive"))
      (node (ref "D61") (pin "2") (pinfunction "K_2") (pintype "passive"))
      (node (ref "D62") (pin "2") (pinfunction "K_2") (pintype "passive"))
      (node (ref "D63") (pin "2") (pinfunction "K_2") (pintype "passive"))
      (node (ref "U1") (pin "1") (pinfunction "PD3_(PCINT19/OC2B/INT1)_1") (pintype "bidirectional"))
    )
    (net (code "24") (name "/R10") (class "Default")
      (node (ref "D64") (pin "2") (pinfunction "K_2") (pintype "passive"))
      (node (ref "D65") (pin "2") (pinfunction "K_2") (pintype "passive"))
      (node (ref "D66") (pin "2") (pinfunction "K_2") (pintype "passive"))
      (node (ref "D67") (pin "2") (pinfunction "K_2") (pintype "passive"))
      (node (ref "D68") (pin "2") (pinfunction "K_2") (pintype "passive"))
      (node (ref "D69") (pin "2") (pinfunction "K_2") (pintype "passive"))
      (node (ref "D70") (pin "2") (pinfunction "K_2") (pintype "passive"))
      (node (ref "U1") (pin "2") (pinfunction "PD4_(PCINT20/XCK/T0)_2") (pintype "bidirectional"))
    )
    (net (code "25") (name "/R11") (class "Default")
      (node (ref "D71") (pin "2") (pinfunction "K_2") (pintype "passive"))
      (node (ref "D72") (pin "2") (pinfunction "K_2") (pintype "passive"))
      (node (ref "D73") (pin "2") (pinfunction "K_2") (pintype "passive"))
      (node (ref "D74") (pin "2") (pinfunction "K_2") (pintype "passive"))
      (node (ref "D75") (pin "2") (pinfunction "K_2") (pintype "passive"))
      (node (ref "D76") (pin "2") (pinfunction "K_2") (pintype "passive"))
      (node (ref "D77") (pin "2") (pinfunction "K_2") (pintype "passive"))
      (node (ref "U1") (pin "13") (pinfunction "PB1_(PCINT1/OC1A)_13") (pintype "bidirectional"))
    )
    (net (code "26") (name "/R12") (class "Default")
      (node (ref "D78") (pin "2") (pinfunction "K_2") (pintype "passive"))
      (node (ref "D79") (pin "2") (pinfunction "K_2") (pintype "passive"))
      (node (ref "D80") (pin "2") (pinfunction "K_2") (pintype "passive"))
      (node (ref "D81") (pin "2") (pinfunction "K_2") (pintype "passive"))
      (node (ref "D82") (pin "2") (pinfunction "K_2") (pintype "passive"))
      (node (ref "D83") (pin "2") (pinfunction "K_2") (pintype "passive"))
      (node (ref "D84") (pin "2") (pinfunction "K_2") (pintype "passive"))
      (node (ref "U1") (pin "12") (pinfunction "PB0_(PCINT0/CLKO/ICP1)_12") (pintype "bidirectional"))
    )
    (net (code "27") (name "/R13") (class "Default")
      (node (ref "D85") (pin "2") (pinfunction "K_2") (pintype "passive"))
      (node (ref "D86") (pin "2") (pinfunction "K_2") (pintype "passive"))
      (node (ref "D87") (pin "2") (pinfunction "K_2") (pintype "passive"))
      (node (ref "D88") (pin "2") (pinfunction "K_2") (pintype "passive"))
      (node (ref "D89") (pin "2") (pinfunction "K_2") (pintype "passive"))
      (node (ref "D90") (pin "2") (pinfunction "K_2") (pintype "passive"))
      (node (ref "D91") (pin "2") (pinfunction "K_2") (pintype "passive"))
      (node (ref "U1") (pin "11") (pinfunction "PD7_(PCINT23/AIN1)_11") (pintype "bidirectional"))
    )
    (net (code "28") (name "/R14") (class "Default")
      (node (ref "D92") (pin "2") (pinfunction "K_2") (pintype "passive"))
      (node (ref "D93") (pin "2") (pinfunction "K_2") (pintype "passive"))
      (node (ref "D94") (pin "2") (pinfunction "K_2") (pintype "passive"))
      (node (ref "D95") (pin "2") (pinfunction "K_2") (pintype "passive"))
      (node (ref "D96") (pin "2") (pinfunction "K_2") (pintype "passive"))
      (node (ref "D97") (pin "2") (pinfunction "K_2") (pintype "passive"))
      (node (ref "D98") (pin "2") (pinfunction "K_2") (pintype "passive"))
      (node (ref "U1") (pin "10") (pinfunction "PD6_(PCINT22/OC0A/AIN0)_10") (pintype "bidirectional"))
    )
    (net (code "29") (name "/R15") (class "Default")
      (node (ref "D100") (pin "2") (pinfunction "K_2") (pintype "passive"))
      (node (ref "D101") (pin "2") (pinfunction "K_2") (pintype "passive"))
      (node (ref "D102") (pin "2") (pinfunction "K_2") (pintype "passive"))
      (node (ref "D103") (pin "2") (pinfunction "K_2") (pintype "passive"))
      (node (ref "D104") (pin "2") (pinfunction "K_2") (pintype "passive"))
      (node (ref "D105") (pin "2") (pinfunction "K_2") (pintype "passive"))
      (node (ref "D99") (pin "2") (pinfunction "K_2") (pintype "passive"))
      (node (ref "U1") (pin "9") (pinfunction "PD5_(PCINT21/OC0B/T1)_9") (pintype "bidirectional"))
    )
    (net (code "30") (name "/RX") (class "Default")
      (node (ref "M1") (pin "3") (pinfunction "D+_3") (pintype "passive"))
      (node (ref "U1") (pin "31") (pinfunction "PD1_(TXD/PCINT17)_31") (pintype "bidirectional"))
    )
    (net (code "31") (name "/TX") (class "Default")
      (node (ref "M1") (pin "2") (pinfunction "D-_2") (pintype "passive"))
      (node (ref "U1") (pin "30") (pinfunction "PD0_(RXD/PCINT16)_30") (pintype "bidirectional"))
    )
    (net (code "32") (name "GND") (class "Default")
      (node (ref "C1") (pin "2") (pinfunction "2_2") (pintype "passive"))
      (node (ref "C2") (pin "2") (pinfunction "2_2") (pintype "passive"))
      (node (ref "C3") (pin "2") (pinfunction "2_2") (pintype "passive"))
      (node (ref "EN") (pin "1") (pintype "passive"))
      (node (ref "F1") (pin "1") (pintype "passive"))
      (node (ref "F2") (pin "1") (pintype "passive"))
      (node (ref "M1") (pin "10") (pinfunction "SHLD5_10") (pintype "passive"))
      (node (ref "M1") (pin "11") (pinfunction "SHLD6_11") (pintype "passive"))
      (node (ref "M1") (pin "5") (pinfunction "GND_5") (pintype "passive"))
      (node (ref "M1") (pin "6") (pinfunction "SHLD1_6") (pintype "passive"))
      (node (ref "M1") (pin "7") (pinfunction "SHLD2_7") (pintype "passive"))
      (node (ref "M1") (pin "8") (pinfunction "SHLD3_8") (pintype "passive"))
      (node (ref "M1") (pin "9") (pinfunction "SHLD4_9") (pintype "passive"))
      (node (ref "U1") (pin "21") (pinfunction "GND_21") (pintype "power_in"))
      (node (ref "U1") (pin "3") (pinfunction "GND_3") (pintype "power_in"))
      (node (ref "U1") (pin "5") (pinfunction "GND_5") (pintype "power_in"))
      (node (ref "U2") (pin "13") (pinfunction "~{OE}_13") (pintype "input"))
      (node (ref "U2") (pin "8") (pinfunction "GND_8") (pintype "power_in"))
      (node (ref "Y1") (pin "2") (pinfunction "GND_2") (pintype "power_in"))
    )
    (net (code "33") (name "Net-(DIO1-A)") (class "Default")
      (node (ref "C2") (pin "1") (pinfunction "1_1") (pintype "passive"))
      (node (ref "C3") (pin "1") (pinfunction "1_1") (pintype "passive"))
      (node (ref "DIO1") (pin "1") (pinfunction "A_1") (pintype "passive"))
      (node (ref "M1") (pin "1") (pinfunction "VBUS_1") (pintype "passive"))
    )
    (net (code "34") (name "Net-(F1-Pad2)") (class "Default")
      (node (ref "F1") (pin "2") (pinfunction "2_2") (pintype "passive"))
      (node (ref "R9") (pin "2") (pinfunction "2_2") (pintype "passive"))
    )
    (net (code "35") (name "Net-(U1-ADC7)") (class "Default")
      (node (ref "F2") (pin "2") (pinfunction "2_2") (pintype "passive"))
      (node (ref "R10") (pin "1") (pinfunction "1_1") (pintype "passive"))
      (node (ref "R9") (pin "1") (pinfunction "1_1") (pintype "passive"))
      (node (ref "U1") (pin "22") (pinfunction "ADC7_22") (pintype "input"))
    )
    (net (code "36") (name "Net-(U1-PB6_(PCINT6{slash}XTAL1{slash}TOSC1))") (class "Default")
      (node (ref "U1") (pin "7") (pinfunction "PB6_(PCINT6/XTAL1/TOSC1)_7") (pintype "bidirectional"))
      (node (ref "Y1") (pin "1") (pinfunction "Input_1") (pintype "input"))
    )
    (net (code "37") (name "Net-(U1-PB7_(PCINT7{slash}XTAL2{slash}TOSC2))") (class "Default")
      (node (ref "U1") (pin "8") (pinfunction "PB7_(PCINT7/XTAL2/TOSC2)_8") (pintype "bidirectional"))
      (node (ref "Y1") (pin "3") (pinfunction "Output_3") (pintype "output"))
    )
    (net (code "38") (name "Net-(U2-Q1)") (class "Default")
      (node (ref "R2") (pin "2") (pinfunction "2_2") (pintype "passive"))
      (node (ref "U2") (pin "1") (pinfunction "Q1_1") (pintype "output"))
    )
    (net (code "39") (name "Net-(U2-Q2)") (class "Default")
      (node (ref "R3") (pin "2") (pinfunction "2_2") (pintype "passive"))
      (node (ref "U2") (pin "2") (pinfunction "Q2_2") (pintype "output"))
    )
    (net (code "40") (name "Net-(U2-Q3)") (class "Default")
      (node (ref "R4") (pin "2") (pinfunction "2_2") (pintype "passive"))
      (node (ref "U2") (pin "3") (pinfunction "Q3_3") (pintype "output"))
    )
    (net (code "41") (name "Net-(U2-Q4)") (class "Default")
      (node (ref "R5") (pin "2") (pinfunction "2_2") (pintype "passive"))
      (node (ref "U2") (pin "4") (pinfunction "Q4_4") (pintype "output"))
    )
    (net (code "42") (name "Net-(U2-Q5)") (class "Default")
      (node (ref "R6") (pin "2") (pinfunction "2_2") (pintype "passive"))
      (node (ref "U2") (pin "5") (pinfunction "Q5_5") (pintype "output"))
    )
    (net (code "43") (name "Net-(U2-Q6)") (class "Default")
      (node (ref "R7") (pin "2") (pinfunction "2_2") (pintype "passive"))
      (node (ref "U2") (pin "6") (pinfunction "Q6_6") (pintype "output"))
    )
    (net (code "44") (name "Net-(U2-Q7)") (class "Default")
      (node (ref "R8") (pin "2") (pinfunction "2_2") (pintype "passive"))
      (node (ref "U2") (pin "7") (pinfunction "Q7_7") (pintype "output"))
    )
    (net (code "45") (name "unconnected-(EN-Pad3)") (class "Default")
      (node (ref "EN") (pin "3") (pinfunction "3_3") (pintype "passive"))
    )
    (net (code "46") (name "unconnected-(EN-Pad4)") (class "Default")
      (node (ref "EN") (pin "4") (pinfunction "4_4") (pintype "passive"))
    )
    (net (code "47") (name "unconnected-(F1-Pad3)") (class "Default")
      (node (ref "F1") (pin "3") (pinfunction "3_3") (pintype "passive"))
    )
    (net (code "48") (name "unconnected-(F1-Pad4)") (class "Default")
      (node (ref "F1") (pin "4") (pinfunction "4_4") (pintype "passive"))
    )
    (net (code "49") (name "unconnected-(F2-Pad3)") (class "Default")
      (node (ref "F2") (pin "3") (pinfunction "3_3") (pintype "passive"))
    )
    (net (code "50") (name "unconnected-(F2-Pad4)") (class "Default")
      (node (ref "F2") (pin "4") (pinfunction "4_4") (pintype "passive"))
    )
    (net (code "51") (name "unconnected-(M1-ID-Pad4)") (class "Default")
      (node (ref "M1") (pin "4") (pinfunction "ID_4") (pintype "passive"))
    )
    (net (code "52") (name "unconnected-(U2-Q0-Pad15)") (class "Default")
      (node (ref "U2") (pin "15") (pinfunction "Q0_15") (pintype "output"))
    )
  )
)
